# led-er-v2_3c.net
KiCad netlist of a schematic drawn in EAGLE
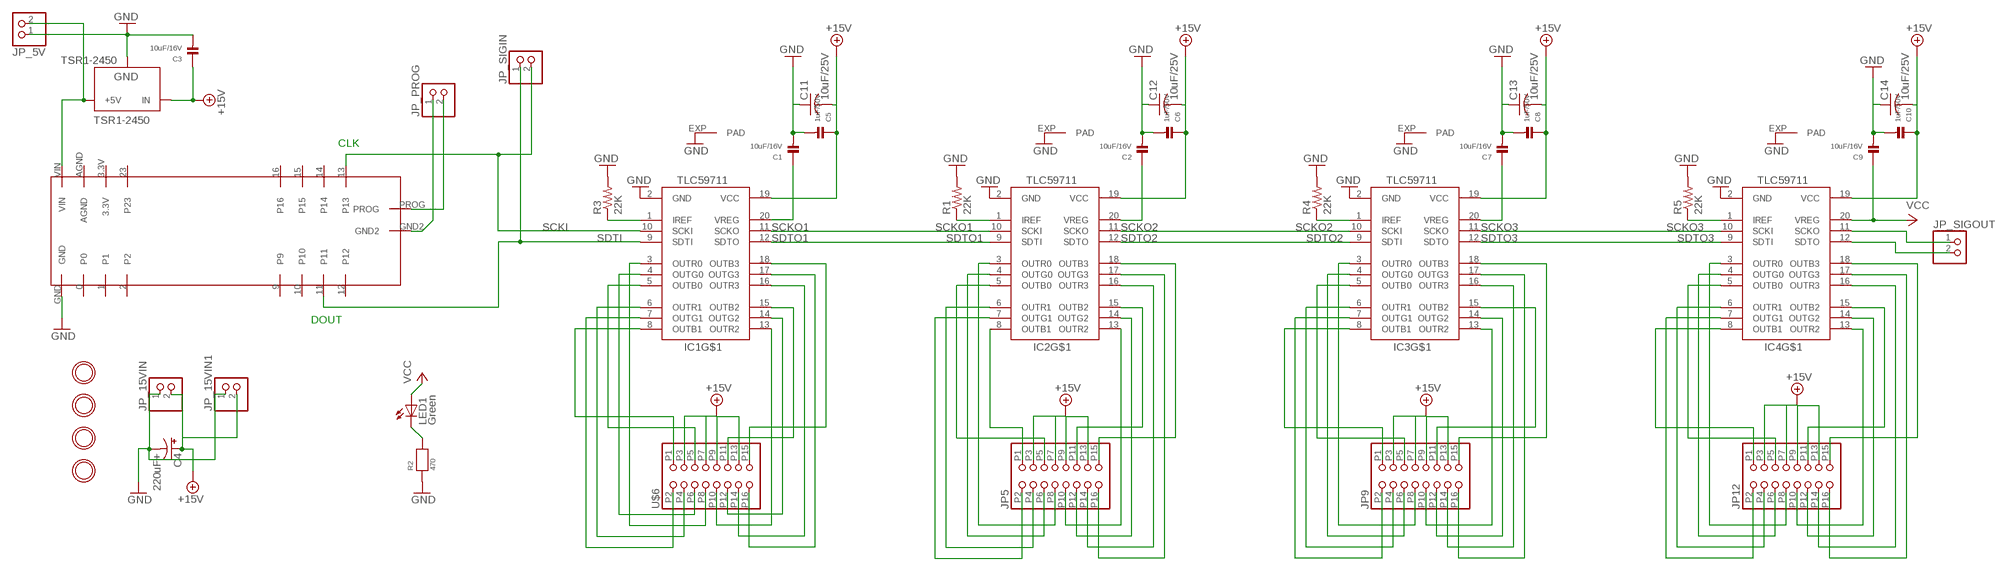
[diagram p0: schematic, sheet 1]

(export (version "E")
  (design (tool "Eeschema 10.0.6"))
  (components
    (comp (ref "C1")
      (value "10uF/16V")
      (footprint "eagle-import:0805")
      (libsource (lib "eagle-import") (part "CAP_CERAMIC0805"))
    )
    (comp (ref "C2")
      (value "10uF/16V")
      (footprint "eagle-import:0805")
      (libsource (lib "eagle-import") (part "CAP_CERAMIC0805"))
    )
    (comp (ref "C3")
      (value "10uF/16V")
      (footprint "eagle-import:0805")
      (libsource (lib "eagle-import") (part "CAP_CERAMIC0805"))
    )
    (comp (ref "C4")
      (value "220uF+")
      (footprint "eagle-import:E5-8,5")
      (libsource (lib "eagle-import") (part "CPOL-USE5-8.5"))
    )
    (comp (ref "C5")
      (value "1uF/50V")
      (footprint "eagle-import:0805")
      (libsource (lib "eagle-import") (part "CAP_CERAMIC0805"))
    )
    (comp (ref "C6")
      (value "1uF/50V")
      (footprint "eagle-import:0805")
      (libsource (lib "eagle-import") (part "CAP_CERAMIC0805"))
    )
    (comp (ref "C7")
      (value "10uF/16V")
      (footprint "eagle-import:0805")
      (libsource (lib "eagle-import") (part "CAP_CERAMIC0805"))
    )
    (comp (ref "C8")
      (value "1uF/50V")
      (footprint "eagle-import:0805")
      (libsource (lib "eagle-import") (part "CAP_CERAMIC0805"))
    )
    (comp (ref "C9")
      (value "10uF/16V")
      (footprint "eagle-import:0805")
      (libsource (lib "eagle-import") (part "CAP_CERAMIC0805"))
    )
    (comp (ref "C10")
      (value "1uF/50V")
      (footprint "eagle-import:0805")
      (libsource (lib "eagle-import") (part "CAP_CERAMIC0805"))
    )
    (comp (ref "C11")
      (value "10uF/25V")
      (footprint "eagle-import:C0805")
      (libsource (lib "eagle-import") (part "C-USC0805"))
    )
    (comp (ref "C12")
      (value "10uF/25V")
      (footprint "eagle-import:C0805")
      (libsource (lib "eagle-import") (part "C-USC0805"))
    )
    (comp (ref "C13")
      (value "10uF/25V")
      (footprint "eagle-import:C0805")
      (libsource (lib "eagle-import") (part "C-USC0805"))
    )
    (comp (ref "C14")
      (value "10uF/25V")
      (footprint "eagle-import:C0805")
      (libsource (lib "eagle-import") (part "C-USC0805"))
    )
    (comp (ref "IC1")
      (value "TLC59711")
      (footprint "eagle-import:HTSSOP20DAP")
      (libsource (lib "eagle-import") (part "TLC59711"))
    )
    (comp (ref "IC2")
      (value "TLC59711")
      (footprint "eagle-import:HTSSOP20DAP")
      (libsource (lib "eagle-import") (part "TLC59711"))
    )
    (comp (ref "IC3")
      (value "TLC59711")
      (footprint "eagle-import:HTSSOP20DAP")
      (libsource (lib "eagle-import") (part "TLC59711"))
    )
    (comp (ref "IC4")
      (value "TLC59711")
      (footprint "eagle-import:HTSSOP20DAP")
      (libsource (lib "eagle-import") (part "TLC59711"))
    )
    (comp (ref "JP5")
      (value "HEADER-2X8-RIBBON")
      (footprint "eagle-import:2X08_RIBBON")
      (libsource (lib "eagle-import") (part "HEADER-2X8-RIBBON"))
    )
    (comp (ref "JP9")
      (value "HEADER-2X8-RIBBON")
      (footprint "eagle-import:2X08_RIBBON")
      (libsource (lib "eagle-import") (part "HEADER-2X8-RIBBON"))
    )
    (comp (ref "JP12")
      (value "HEADER-2X8-RIBBON")
      (footprint "eagle-import:2X08_RIBBON")
      (libsource (lib "eagle-import") (part "HEADER-2X8-RIBBON"))
    )
    (comp (ref "JP_5V")
      (value "HEADER-1X2")
      (footprint "eagle-import:1X02_OVAL")
      (libsource (lib "eagle-import") (part "HEADER-1X2"))
    )
    (comp (ref "JP_15VIN")
      (value "HEADER-1X2")
      (footprint "eagle-import:1X02_OVAL")
      (libsource (lib "eagle-import") (part "HEADER-1X2"))
    )
    (comp (ref "JP_15VIN1")
      (value "HEADER-1X2")
      (footprint "eagle-import:1X02_OVAL")
      (libsource (lib "eagle-import") (part "HEADER-1X2"))
    )
    (comp (ref "JP_PROG")
      (value "HEADER-1X2")
      (footprint "eagle-import:1X02_OVAL")
      (libsource (lib "eagle-import") (part "HEADER-1X2"))
    )
    (comp (ref "JP_SIGIN")
      (value "HEADER-1X2")
      (footprint "eagle-import:1X02_OVAL")
      (libsource (lib "eagle-import") (part "HEADER-1X2"))
    )
    (comp (ref "JP_SIGOUT")
      (value "HEADER-1X2")
      (footprint "eagle-import:1X02_OVAL")
      (libsource (lib "eagle-import") (part "HEADER-1X2"))
    )
    (comp (ref "LED1")
      (value "Green")
      (footprint "eagle-import:CHIP-LED0805")
      (libsource (lib "eagle-import") (part "LEDCHIP-LED0805"))
    )
    (comp (ref "R1")
      (value "22K")
      (footprint "eagle-import:0805-THM-7")
      (libsource (lib "eagle-import") (part "R-US_FLIPFLOP7"))
    )
    (comp (ref "R2")
      (value "470")
      (footprint "eagle-import:0805")
      (libsource (lib "eagle-import") (part "RESISTOR0805"))
    )
    (comp (ref "R3")
      (value "22K")
      (footprint "eagle-import:0805-THM-7")
      (libsource (lib "eagle-import") (part "R-US_FLIPFLOP7"))
    )
    (comp (ref "R4")
      (value "22K")
      (footprint "eagle-import:0805-THM-7")
      (libsource (lib "eagle-import") (part "R-US_FLIPFLOP7"))
    )
    (comp (ref "R5")
      (value "22K")
      (footprint "eagle-import:0805-THM-7")
      (libsource (lib "eagle-import") (part "R-US_FLIPFLOP7"))
    )
    (comp (ref "TSR1-2450")
      (value "TSR1-2450")
      (footprint "eagle-import:TSR-1")
      (libsource (lib "eagle-import") (part "TSR1-2450"))
    )
    (comp (ref "U$1")
      (value "MOUNTINGHOLE")
      (footprint "eagle-import:MOUNTINGHOLE_3.0_PLATED")
      (libsource (lib "eagle-import") (part "MOUNTINGHOLE"))
    )
    (comp (ref "U$2")
      (value "MOUNTINGHOLE")
      (footprint "eagle-import:MOUNTINGHOLE_3.0_PLATED")
      (libsource (lib "eagle-import") (part "MOUNTINGHOLE"))
    )
    (comp (ref "U$3")
      (value "MOUNTINGHOLE")
      (footprint "eagle-import:MOUNTINGHOLE_3.0_PLATED")
      (libsource (lib "eagle-import") (part "MOUNTINGHOLE"))
    )
    (comp (ref "U$4")
      (value "MOUNTINGHOLE")
      (footprint "eagle-import:MOUNTINGHOLE_3.0_PLATED")
      (libsource (lib "eagle-import") (part "MOUNTINGHOLE"))
    )
    (comp (ref "U$5")
      (value "TEENSY_LEDER")
      (footprint "eagle-import:TEENSY_LEDER")
      (libsource (lib "eagle-import") (part "TEENSY_LEDER"))
    )
    (comp (ref "U$6")
      (value "HEADER-2X8-RIBBON")
      (footprint "eagle-import:2X08_RIBBON")
      (libsource (lib "eagle-import") (part "HEADER-2X8-RIBBON"))
    )
  )
  (nets
    (net (code "1") (name "+15V") (class "Default")
      (node (ref "C10") (pin "1") (pinfunction "P$1_1") (pintype "passive"))
      (node (ref "C11") (pin "2") (pinfunction "2_2") (pintype "passive"))
      (node (ref "C12") (pin "2") (pinfunction "2_2") (pintype "passive"))
      (node (ref "C13") (pin "2") (pinfunction "2_2") (pintype "passive"))
      (node (ref "C14") (pin "2") (pinfunction "2_2") (pintype "passive"))
      (node (ref "C3") (pin "1") (pinfunction "P$1_1") (pintype "passive"))
      (node (ref "C4") (pin "+") (pinfunction "+_+") (pintype "passive"))
      (node (ref "C5") (pin "1") (pinfunction "P$1_1") (pintype "passive"))
      (node (ref "C6") (pin "1") (pinfunction "P$1_1") (pintype "passive"))
      (node (ref "C8") (pin "1") (pinfunction "P$1_1") (pintype "passive"))
      (node (ref "IC1") (pin "19") (pinfunction "VCC_19") (pintype "power_in"))
      (node (ref "IC2") (pin "19") (pinfunction "VCC_19") (pintype "power_in"))
      (node (ref "IC3") (pin "19") (pinfunction "VCC_19") (pintype "power_in"))
      (node (ref "IC4") (pin "19") (pinfunction "VCC_19") (pintype "power_in"))
      (node (ref "JP12") (pin "P13") (pinfunction "P13_P13") (pintype "passive"))
      (node (ref "JP12") (pin "P3") (pinfunction "P3_P3") (pintype "passive"))
      (node (ref "JP12") (pin "P7") (pinfunction "P7_P7") (pintype "passive"))
      (node (ref "JP12") (pin "P9") (pinfunction "P9_P9") (pintype "passive"))
      (node (ref "JP5") (pin "P13") (pinfunction "P13_P13") (pintype "passive"))
      (node (ref "JP5") (pin "P3") (pinfunction "P3_P3") (pintype "passive"))
      (node (ref "JP5") (pin "P7") (pinfunction "P7_P7") (pintype "passive"))
      (node (ref "JP5") (pin "P9") (pinfunction "P9_P9") (pintype "passive"))
      (node (ref "JP9") (pin "P13") (pinfunction "P13_P13") (pintype "passive"))
      (node (ref "JP9") (pin "P3") (pinfunction "P3_P3") (pintype "passive"))
      (node (ref "JP9") (pin "P7") (pinfunction "P7_P7") (pintype "passive"))
      (node (ref "JP9") (pin "P9") (pinfunction "P9_P9") (pintype "passive"))
      (node (ref "JP_15VIN") (pin "2") (pinfunction "2_2") (pintype "passive"))
      (node (ref "JP_15VIN1") (pin "2") (pinfunction "2_2") (pintype "passive"))
      (node (ref "TSR1-2450") (pin "1") (pinfunction "IN_1") (pintype "power_in"))
      (node (ref "U$6") (pin "P13") (pinfunction "P13_P13") (pintype "passive"))
      (node (ref "U$6") (pin "P3") (pinfunction "P3_P3") (pintype "passive"))
      (node (ref "U$6") (pin "P7") (pinfunction "P7_P7") (pintype "passive"))
      (node (ref "U$6") (pin "P9") (pinfunction "P9_P9") (pintype "passive"))
    )
    (net (code "2") (name "/SCKI") (class "Default")
      (node (ref "IC1") (pin "10") (pinfunction "SCKI_10") (pintype "input"))
      (node (ref "JP_SIGIN") (pin "2") (pinfunction "2_2") (pintype "passive"))
      (node (ref "U$5") (pin "13") (pinfunction "P13_13") (pintype "bidirectional"))
    )
    (net (code "3") (name "/SCKO1") (class "Default")
      (node (ref "IC1") (pin "11") (pinfunction "SCKO_11") (pintype "output"))
      (node (ref "IC2") (pin "10") (pinfunction "SCKI_10") (pintype "input"))
    )
    (net (code "4") (name "/SCKO2") (class "Default")
      (node (ref "IC2") (pin "11") (pinfunction "SCKO_11") (pintype "output"))
      (node (ref "IC3") (pin "10") (pinfunction "SCKI_10") (pintype "input"))
    )
    (net (code "5") (name "/SCKO3") (class "Default")
      (node (ref "IC3") (pin "11") (pinfunction "SCKO_11") (pintype "output"))
      (node (ref "IC4") (pin "10") (pinfunction "SCKI_10") (pintype "input"))
    )
    (net (code "6") (name "/SDTI") (class "Default")
      (node (ref "IC1") (pin "9") (pinfunction "SDTI_9") (pintype "input"))
      (node (ref "JP_SIGIN") (pin "1") (pinfunction "1_1") (pintype "passive"))
      (node (ref "U$5") (pin "11") (pinfunction "P11_11") (pintype "bidirectional"))
    )
    (net (code "7") (name "/SDTO1") (class "Default")
      (node (ref "IC1") (pin "12") (pinfunction "SDTO_12") (pintype "output"))
      (node (ref "IC2") (pin "9") (pinfunction "SDTI_9") (pintype "input"))
    )
    (net (code "8") (name "/SDTO2") (class "Default")
      (node (ref "IC2") (pin "12") (pinfunction "SDTO_12") (pintype "output"))
      (node (ref "IC3") (pin "9") (pinfunction "SDTI_9") (pintype "input"))
    )
    (net (code "9") (name "/SDTO3") (class "Default")
      (node (ref "IC3") (pin "12") (pinfunction "SDTO_12") (pintype "output"))
      (node (ref "IC4") (pin "9") (pinfunction "SDTI_9") (pintype "input"))
    )
    (net (code "10") (name "GND") (class "Default")
      (node (ref "C1") (pin "2") (pinfunction "P$2_2") (pintype "passive"))
      (node (ref "C10") (pin "2") (pinfunction "P$2_2") (pintype "passive"))
      (node (ref "C11") (pin "1") (pinfunction "1_1") (pintype "passive"))
      (node (ref "C12") (pin "1") (pinfunction "1_1") (pintype "passive"))
      (node (ref "C13") (pin "1") (pinfunction "1_1") (pintype "passive"))
      (node (ref "C14") (pin "1") (pinfunction "1_1") (pintype "passive"))
      (node (ref "C2") (pin "2") (pinfunction "P$2_2") (pintype "passive"))
      (node (ref "C3") (pin "2") (pinfunction "P$2_2") (pintype "passive"))
      (node (ref "C4") (pin "-") (pinfunction "-_-") (pintype "passive"))
      (node (ref "C5") (pin "2") (pinfunction "P$2_2") (pintype "passive"))
      (node (ref "C6") (pin "2") (pinfunction "P$2_2") (pintype "passive"))
      (node (ref "C7") (pin "2") (pinfunction "P$2_2") (pintype "passive"))
      (node (ref "C8") (pin "2") (pinfunction "P$2_2") (pintype "passive"))
      (node (ref "C9") (pin "2") (pinfunction "P$2_2") (pintype "passive"))
      (node (ref "IC1") (pin "2") (pinfunction "GND_2") (pintype "power_in"))
      (node (ref "IC1") (pin "EXP") (pinfunction "PAD_EXP") (pintype "passive"))
      (node (ref "IC2") (pin "2") (pinfunction "GND_2") (pintype "power_in"))
      (node (ref "IC2") (pin "EXP") (pinfunction "PAD_EXP") (pintype "passive"))
      (node (ref "IC3") (pin "2") (pinfunction "GND_2") (pintype "power_in"))
      (node (ref "IC3") (pin "EXP") (pinfunction "PAD_EXP") (pintype "passive"))
      (node (ref "IC4") (pin "2") (pinfunction "GND_2") (pintype "power_in"))
      (node (ref "IC4") (pin "EXP") (pinfunction "PAD_EXP") (pintype "passive"))
      (node (ref "JP_15VIN") (pin "1") (pinfunction "1_1") (pintype "passive"))
      (node (ref "JP_15VIN1") (pin "1") (pinfunction "1_1") (pintype "passive"))
      (node (ref "JP_5V") (pin "1") (pinfunction "1_1") (pintype "passive"))
      (node (ref "R1") (pin "2") (pinfunction "2_2") (pintype "passive"))
      (node (ref "R2") (pin "1") (pinfunction "1_1") (pintype "passive"))
      (node (ref "R3") (pin "2") (pinfunction "2_2") (pintype "passive"))
      (node (ref "R4") (pin "2") (pinfunction "2_2") (pintype "passive"))
      (node (ref "R5") (pin "2") (pinfunction "2_2") (pintype "passive"))
      (node (ref "TSR1-2450") (pin "2") (pinfunction "GND_2") (pintype "power_in"))
      (node (ref "U$5") (pin "GND") (pinfunction "GND_GND") (pintype "bidirectional"))
    )
    (net (code "11") (name "Net-(C1-P$1)") (class "Default")
      (node (ref "C1") (pin "1") (pinfunction "P$1_1") (pintype "passive"))
      (node (ref "IC1") (pin "20") (pinfunction "VREG_20") (pintype "bidirectional"))
    )
    (net (code "12") (name "Net-(C2-P$1)") (class "Default")
      (node (ref "C2") (pin "1") (pinfunction "P$1_1") (pintype "passive"))
      (node (ref "IC2") (pin "20") (pinfunction "VREG_20") (pintype "bidirectional"))
    )
    (net (code "13") (name "Net-(C7-P$1)") (class "Default")
      (node (ref "C7") (pin "1") (pinfunction "P$1_1") (pintype "passive"))
      (node (ref "IC3") (pin "20") (pinfunction "VREG_20") (pintype "bidirectional"))
    )
    (net (code "14") (name "Net-(IC1A-IREF)") (class "Default")
      (node (ref "IC1") (pin "1") (pinfunction "IREF_1") (pintype "bidirectional"))
      (node (ref "R3") (pin "1") (pinfunction "1_1") (pintype "passive"))
    )
    (net (code "15") (name "Net-(IC1A-OUTB0)") (class "Default")
      (node (ref "IC1") (pin "5") (pinfunction "OUTB0_5") (pintype "open_collector"))
      (node (ref "U$6") (pin "P5") (pinfunction "P5_P5") (pintype "passive"))
    )
    (net (code "16") (name "Net-(IC1A-OUTB1)") (class "Default")
      (node (ref "IC1") (pin "8") (pinfunction "OUTB1_8") (pintype "open_collector"))
      (node (ref "U$6") (pin "P1") (pinfunction "P1_P1") (pintype "passive"))
    )
    (net (code "17") (name "Net-(IC1A-OUTB2)") (class "Default")
      (node (ref "IC1") (pin "15") (pinfunction "OUTB2_15") (pintype "open_collector"))
      (node (ref "U$6") (pin "P11") (pinfunction "P11_P11") (pintype "passive"))
    )
    (net (code "18") (name "Net-(IC1A-OUTB3)") (class "Default")
      (node (ref "IC1") (pin "18") (pinfunction "OUTB3_18") (pintype "open_collector"))
      (node (ref "U$6") (pin "P15") (pinfunction "P15_P15") (pintype "passive"))
    )
    (net (code "19") (name "Net-(IC1A-OUTG0)") (class "Default")
      (node (ref "IC1") (pin "4") (pinfunction "OUTG0_4") (pintype "open_collector"))
      (node (ref "U$6") (pin "P6") (pinfunction "P6_P6") (pintype "passive"))
    )
    (net (code "20") (name "Net-(IC1A-OUTG1)") (class "Default")
      (node (ref "IC1") (pin "7") (pinfunction "OUTG1_7") (pintype "open_collector"))
      (node (ref "U$6") (pin "P2") (pinfunction "P2_P2") (pintype "passive"))
    )
    (net (code "21") (name "Net-(IC1A-OUTG2)") (class "Default")
      (node (ref "IC1") (pin "14") (pinfunction "OUTG2_14") (pintype "open_collector"))
      (node (ref "U$6") (pin "P12") (pinfunction "P12_P12") (pintype "passive"))
    )
    (net (code "22") (name "Net-(IC1A-OUTG3)") (class "Default")
      (node (ref "IC1") (pin "17") (pinfunction "OUTG3_17") (pintype "open_collector"))
      (node (ref "U$6") (pin "P16") (pinfunction "P16_P16") (pintype "passive"))
    )
    (net (code "23") (name "Net-(IC1A-OUTR0)") (class "Default")
      (node (ref "IC1") (pin "3") (pinfunction "OUTR0_3") (pintype "open_collector"))
      (node (ref "U$6") (pin "P8") (pinfunction "P8_P8") (pintype "passive"))
    )
    (net (code "24") (name "Net-(IC1A-OUTR1)") (class "Default")
      (node (ref "IC1") (pin "6") (pinfunction "OUTR1_6") (pintype "open_collector"))
      (node (ref "U$6") (pin "P4") (pinfunction "P4_P4") (pintype "passive"))
    )
    (net (code "25") (name "Net-(IC1A-OUTR2)") (class "Default")
      (node (ref "IC1") (pin "13") (pinfunction "OUTR2_13") (pintype "open_collector"))
      (node (ref "U$6") (pin "P10") (pinfunction "P10_P10") (pintype "passive"))
    )
    (net (code "26") (name "Net-(IC1A-OUTR3)") (class "Default")
      (node (ref "IC1") (pin "16") (pinfunction "OUTR3_16") (pintype "open_collector"))
      (node (ref "U$6") (pin "P14") (pinfunction "P14_P14") (pintype "passive"))
    )
    (net (code "27") (name "Net-(IC2A-IREF)") (class "Default")
      (node (ref "IC2") (pin "1") (pinfunction "IREF_1") (pintype "bidirectional"))
      (node (ref "R1") (pin "1") (pinfunction "1_1") (pintype "passive"))
    )
    (net (code "28") (name "Net-(IC2A-OUTB0)") (class "Default")
      (node (ref "IC2") (pin "5") (pinfunction "OUTB0_5") (pintype "open_collector"))
      (node (ref "JP5") (pin "P5") (pinfunction "P5_P5") (pintype "passive"))
    )
    (net (code "29") (name "Net-(IC2A-OUTB1)") (class "Default")
      (node (ref "IC2") (pin "8") (pinfunction "OUTB1_8") (pintype "open_collector"))
      (node (ref "JP5") (pin "P1") (pinfunction "P1_P1") (pintype "passive"))
    )
    (net (code "30") (name "Net-(IC2A-OUTB2)") (class "Default")
      (node (ref "IC2") (pin "15") (pinfunction "OUTB2_15") (pintype "open_collector"))
      (node (ref "JP5") (pin "P11") (pinfunction "P11_P11") (pintype "passive"))
    )
    (net (code "31") (name "Net-(IC2A-OUTB3)") (class "Default")
      (node (ref "IC2") (pin "18") (pinfunction "OUTB3_18") (pintype "open_collector"))
      (node (ref "JP5") (pin "P15") (pinfunction "P15_P15") (pintype "passive"))
    )
    (net (code "32") (name "Net-(IC2A-OUTG0)") (class "Default")
      (node (ref "IC2") (pin "4") (pinfunction "OUTG0_4") (pintype "open_collector"))
      (node (ref "JP5") (pin "P6") (pinfunction "P6_P6") (pintype "passive"))
    )
    (net (code "33") (name "Net-(IC2A-OUTG1)") (class "Default")
      (node (ref "IC2") (pin "7") (pinfunction "OUTG1_7") (pintype "open_collector"))
      (node (ref "JP5") (pin "P2") (pinfunction "P2_P2") (pintype "passive"))
    )
    (net (code "34") (name "Net-(IC2A-OUTG2)") (class "Default")
      (node (ref "IC2") (pin "14") (pinfunction "OUTG2_14") (pintype "open_collector"))
      (node (ref "JP5") (pin "P12") (pinfunction "P12_P12") (pintype "passive"))
    )
    (net (code "35") (name "Net-(IC2A-OUTG3)") (class "Default")
      (node (ref "IC2") (pin "17") (pinfunction "OUTG3_17") (pintype "open_collector"))
      (node (ref "JP5") (pin "P16") (pinfunction "P16_P16") (pintype "passive"))
    )
    (net (code "36") (name "Net-(IC2A-OUTR0)") (class "Default")
      (node (ref "IC2") (pin "3") (pinfunction "OUTR0_3") (pintype "open_collector"))
      (node (ref "JP5") (pin "P8") (pinfunction "P8_P8") (pintype "passive"))
    )
    (net (code "37") (name "Net-(IC2A-OUTR1)") (class "Default")
      (node (ref "IC2") (pin "6") (pinfunction "OUTR1_6") (pintype "open_collector"))
      (node (ref "JP5") (pin "P4") (pinfunction "P4_P4") (pintype "passive"))
    )
    (net (code "38") (name "Net-(IC2A-OUTR2)") (class "Default")
      (node (ref "IC2") (pin "13") (pinfunction "OUTR2_13") (pintype "open_collector"))
      (node (ref "JP5") (pin "P10") (pinfunction "P10_P10") (pintype "passive"))
    )
    (net (code "39") (name "Net-(IC2A-OUTR3)") (class "Default")
      (node (ref "IC2") (pin "16") (pinfunction "OUTR3_16") (pintype "open_collector"))
      (node (ref "JP5") (pin "P14") (pinfunction "P14_P14") (pintype "passive"))
    )
    (net (code "40") (name "Net-(IC3A-IREF)") (class "Default")
      (node (ref "IC3") (pin "1") (pinfunction "IREF_1") (pintype "bidirectional"))
      (node (ref "R4") (pin "1") (pinfunction "1_1") (pintype "passive"))
    )
    (net (code "41") (name "Net-(IC3A-OUTB0)") (class "Default")
      (node (ref "IC3") (pin "5") (pinfunction "OUTB0_5") (pintype "open_collector"))
      (node (ref "JP9") (pin "P5") (pinfunction "P5_P5") (pintype "passive"))
    )
    (net (code "42") (name "Net-(IC3A-OUTB1)") (class "Default")
      (node (ref "IC3") (pin "8") (pinfunction "OUTB1_8") (pintype "open_collector"))
      (node (ref "JP9") (pin "P1") (pinfunction "P1_P1") (pintype "passive"))
    )
    (net (code "43") (name "Net-(IC3A-OUTB2)") (class "Default")
      (node (ref "IC3") (pin "15") (pinfunction "OUTB2_15") (pintype "open_collector"))
      (node (ref "JP9") (pin "P11") (pinfunction "P11_P11") (pintype "passive"))
    )
    (net (code "44") (name "Net-(IC3A-OUTB3)") (class "Default")
      (node (ref "IC3") (pin "18") (pinfunction "OUTB3_18") (pintype "open_collector"))
      (node (ref "JP9") (pin "P15") (pinfunction "P15_P15") (pintype "passive"))
    )
    (net (code "45") (name "Net-(IC3A-OUTG0)") (class "Default")
      (node (ref "IC3") (pin "4") (pinfunction "OUTG0_4") (pintype "open_collector"))
      (node (ref "JP9") (pin "P6") (pinfunction "P6_P6") (pintype "passive"))
    )
    (net (code "46") (name "Net-(IC3A-OUTG1)") (class "Default")
      (node (ref "IC3") (pin "7") (pinfunction "OUTG1_7") (pintype "open_collector"))
      (node (ref "JP9") (pin "P2") (pinfunction "P2_P2") (pintype "passive"))
    )
    (net (code "47") (name "Net-(IC3A-OUTG2)") (class "Default")
      (node (ref "IC3") (pin "14") (pinfunction "OUTG2_14") (pintype "open_collector"))
      (node (ref "JP9") (pin "P12") (pinfunction "P12_P12") (pintype "passive"))
    )
    (net (code "48") (name "Net-(IC3A-OUTG3)") (class "Default")
      (node (ref "IC3") (pin "17") (pinfunction "OUTG3_17") (pintype "open_collector"))
      (node (ref "JP9") (pin "P16") (pinfunction "P16_P16") (pintype "passive"))
    )
    (net (code "49") (name "Net-(IC3A-OUTR0)") (class "Default")
      (node (ref "IC3") (pin "3") (pinfunction "OUTR0_3") (pintype "open_collector"))
      (node (ref "JP9") (pin "P8") (pinfunction "P8_P8") (pintype "passive"))
    )
    (net (code "50") (name "Net-(IC3A-OUTR1)") (class "Default")
      (node (ref "IC3") (pin "6") (pinfunction "OUTR1_6") (pintype "open_collector"))
      (node (ref "JP9") (pin "P4") (pinfunction "P4_P4") (pintype "passive"))
    )
    (net (code "51") (name "Net-(IC3A-OUTR2)") (class "Default")
      (node (ref "IC3") (pin "13") (pinfunction "OUTR2_13") (pintype "open_collector"))
      (node (ref "JP9") (pin "P10") (pinfunction "P10_P10") (pintype "passive"))
    )
    (net (code "52") (name "Net-(IC3A-OUTR3)") (class "Default")
      (node (ref "IC3") (pin "16") (pinfunction "OUTR3_16") (pintype "open_collector"))
      (node (ref "JP9") (pin "P14") (pinfunction "P14_P14") (pintype "passive"))
    )
    (net (code "53") (name "Net-(IC4A-IREF)") (class "Default")
      (node (ref "IC4") (pin "1") (pinfunction "IREF_1") (pintype "bidirectional"))
      (node (ref "R5") (pin "1") (pinfunction "1_1") (pintype "passive"))
    )
    (net (code "54") (name "Net-(IC4A-OUTB0)") (class "Default")
      (node (ref "IC4") (pin "5") (pinfunction "OUTB0_5") (pintype "open_collector"))
      (node (ref "JP12") (pin "P5") (pinfunction "P5_P5") (pintype "passive"))
    )
    (net (code "55") (name "Net-(IC4A-OUTB1)") (class "Default")
      (node (ref "IC4") (pin "8") (pinfunction "OUTB1_8") (pintype "open_collector"))
      (node (ref "JP12") (pin "P1") (pinfunction "P1_P1") (pintype "passive"))
    )
    (net (code "56") (name "Net-(IC4A-OUTB2)") (class "Default")
      (node (ref "IC4") (pin "15") (pinfunction "OUTB2_15") (pintype "open_collector"))
      (node (ref "JP12") (pin "P11") (pinfunction "P11_P11") (pintype "passive"))
    )
    (net (code "57") (name "Net-(IC4A-OUTB3)") (class "Default")
      (node (ref "IC4") (pin "18") (pinfunction "OUTB3_18") (pintype "open_collector"))
      (node (ref "JP12") (pin "P15") (pinfunction "P15_P15") (pintype "passive"))
    )
    (net (code "58") (name "Net-(IC4A-OUTG0)") (class "Default")
      (node (ref "IC4") (pin "4") (pinfunction "OUTG0_4") (pintype "open_collector"))
      (node (ref "JP12") (pin "P6") (pinfunction "P6_P6") (pintype "passive"))
    )
    (net (code "59") (name "Net-(IC4A-OUTG1)") (class "Default")
      (node (ref "IC4") (pin "7") (pinfunction "OUTG1_7") (pintype "open_collector"))
      (node (ref "JP12") (pin "P2") (pinfunction "P2_P2") (pintype "passive"))
    )
    (net (code "60") (name "Net-(IC4A-OUTG2)") (class "Default")
      (node (ref "IC4") (pin "14") (pinfunction "OUTG2_14") (pintype "open_collector"))
      (node (ref "JP12") (pin "P12") (pinfunction "P12_P12") (pintype "passive"))
    )
    (net (code "61") (name "Net-(IC4A-OUTG3)") (class "Default")
      (node (ref "IC4") (pin "17") (pinfunction "OUTG3_17") (pintype "open_collector"))
      (node (ref "JP12") (pin "P16") (pinfunction "P16_P16") (pintype "passive"))
    )
    (net (code "62") (name "Net-(IC4A-OUTR0)") (class "Default")
      (node (ref "IC4") (pin "3") (pinfunction "OUTR0_3") (pintype "open_collector"))
      (node (ref "JP12") (pin "P8") (pinfunction "P8_P8") (pintype "passive"))
    )
    (net (code "63") (name "Net-(IC4A-OUTR1)") (class "Default")
      (node (ref "IC4") (pin "6") (pinfunction "OUTR1_6") (pintype "open_collector"))
      (node (ref "JP12") (pin "P4") (pinfunction "P4_P4") (pintype "passive"))
    )
    (net (code "64") (name "Net-(IC4A-OUTR2)") (class "Default")
      (node (ref "IC4") (pin "13") (pinfunction "OUTR2_13") (pintype "open_collector"))
      (node (ref "JP12") (pin "P10") (pinfunction "P10_P10") (pintype "passive"))
    )
    (net (code "65") (name "Net-(IC4A-OUTR3)") (class "Default")
      (node (ref "IC4") (pin "16") (pinfunction "OUTR3_16") (pintype "open_collector"))
      (node (ref "JP12") (pin "P14") (pinfunction "P14_P14") (pintype "passive"))
    )
    (net (code "66") (name "Net-(IC4A-SCKO)") (class "Default")
      (node (ref "IC4") (pin "11") (pinfunction "SCKO_11") (pintype "output"))
      (node (ref "JP_SIGOUT") (pin "1") (pinfunction "1_1") (pintype "passive"))
    )
    (net (code "67") (name "Net-(IC4A-SDTO)") (class "Default")
      (node (ref "IC4") (pin "12") (pinfunction "SDTO_12") (pintype "output"))
      (node (ref "JP_SIGOUT") (pin "2") (pinfunction "2_2") (pintype "passive"))
    )
    (net (code "68") (name "Net-(JP_PROG-Pad1)") (class "Default")
      (node (ref "JP_PROG") (pin "1") (pinfunction "1_1") (pintype "passive"))
      (node (ref "U$5") (pin "GND2") (pinfunction "GND2_GND2") (pintype "bidirectional"))
    )
    (net (code "69") (name "Net-(JP_PROG-Pad2)") (class "Default")
      (node (ref "JP_PROG") (pin "2") (pinfunction "2_2") (pintype "passive"))
      (node (ref "U$5") (pin "PROG") (pinfunction "PROG_PROG") (pintype "bidirectional"))
    )
    (net (code "70") (name "Net-(LED1-PadC)") (class "Default")
      (node (ref "LED1") (pin "C") (pinfunction "C_C") (pintype "passive"))
      (node (ref "R2") (pin "2") (pinfunction "2_2") (pintype "passive"))
    )
    (net (code "71") (name "Net-(TSR1-2450-+5V)") (class "Default")
      (node (ref "JP_5V") (pin "2") (pinfunction "2_2") (pintype "passive"))
      (node (ref "TSR1-2450") (pin "3") (pinfunction "+5V_3") (pintype "power_in"))
      (node (ref "U$5") (pin "VIN") (pinfunction "VIN_VIN") (pintype "bidirectional"))
    )
    (net (code "72") (name "VCC") (class "Default")
      (node (ref "C9") (pin "1") (pinfunction "P$1_1") (pintype "passive"))
      (node (ref "IC4") (pin "20") (pinfunction "VREG_20") (pintype "bidirectional"))
      (node (ref "LED1") (pin "A") (pinfunction "A_A") (pintype "passive"))
    )
    (net (code "73") (name "unconnected-(U$5-P0-Pad0)") (class "Default")
      (node (ref "U$5") (pin "0") (pinfunction "P0_0") (pintype "bidirectional"))
    )
    (net (code "74") (name "unconnected-(U$5-P1-Pad1)") (class "Default")
      (node (ref "U$5") (pin "1") (pinfunction "P1_1") (pintype "bidirectional"))
    )
    (net (code "75") (name "unconnected-(U$5-P2-Pad2)") (class "Default")
      (node (ref "U$5") (pin "2") (pinfunction "P2_2") (pintype "bidirectional"))
    )
    (net (code "76") (name "unconnected-(U$5-P9-Pad9)") (class "Default")
      (node (ref "U$5") (pin "9") (pinfunction "P9_9") (pintype "bidirectional"))
    )
    (net (code "77") (name "unconnected-(U$5-P10-Pad10)") (class "Default")
      (node (ref "U$5") (pin "10") (pinfunction "P10_10") (pintype "bidirectional"))
    )
    (net (code "78") (name "unconnected-(U$5-P12-Pad12)") (class "Default")
      (node (ref "U$5") (pin "12") (pinfunction "P12_12") (pintype "bidirectional"))
    )
    (net (code "79") (name "unconnected-(U$5-P14-Pad14)") (class "Default")
      (node (ref "U$5") (pin "14") (pinfunction "P14_14") (pintype "bidirectional"))
    )
    (net (code "80") (name "unconnected-(U$5-P15-Pad15)") (class "Default")
      (node (ref "U$5") (pin "15") (pinfunction "P15_15") (pintype "bidirectional"))
    )
    (net (code "81") (name "unconnected-(U$5-P16-Pad16)") (class "Default")
      (node (ref "U$5") (pin "16") (pinfunction "P16_16") (pintype "bidirectional"))
    )
    (net (code "82") (name "unconnected-(U$5-P23-Pad23)") (class "Default")
      (node (ref "U$5") (pin "23") (pinfunction "P23_23") (pintype "bidirectional"))
    )
    (net (code "83") (name "unconnected-(U$5-Pad3.3V)") (class "Default")
      (node (ref "U$5") (pin "3.3V") (pinfunction "3.3V_3.3V") (pintype "bidirectional"))
    )
    (net (code "84") (name "unconnected-(U$5-PadAGND)") (class "Default")
      (node (ref "U$5") (pin "AGND") (pinfunction "AGND_AGND") (pintype "bidirectional"))
    )
  )
)
